# gimbal.net
KiCad netlist of a schematic drawn in EAGLE
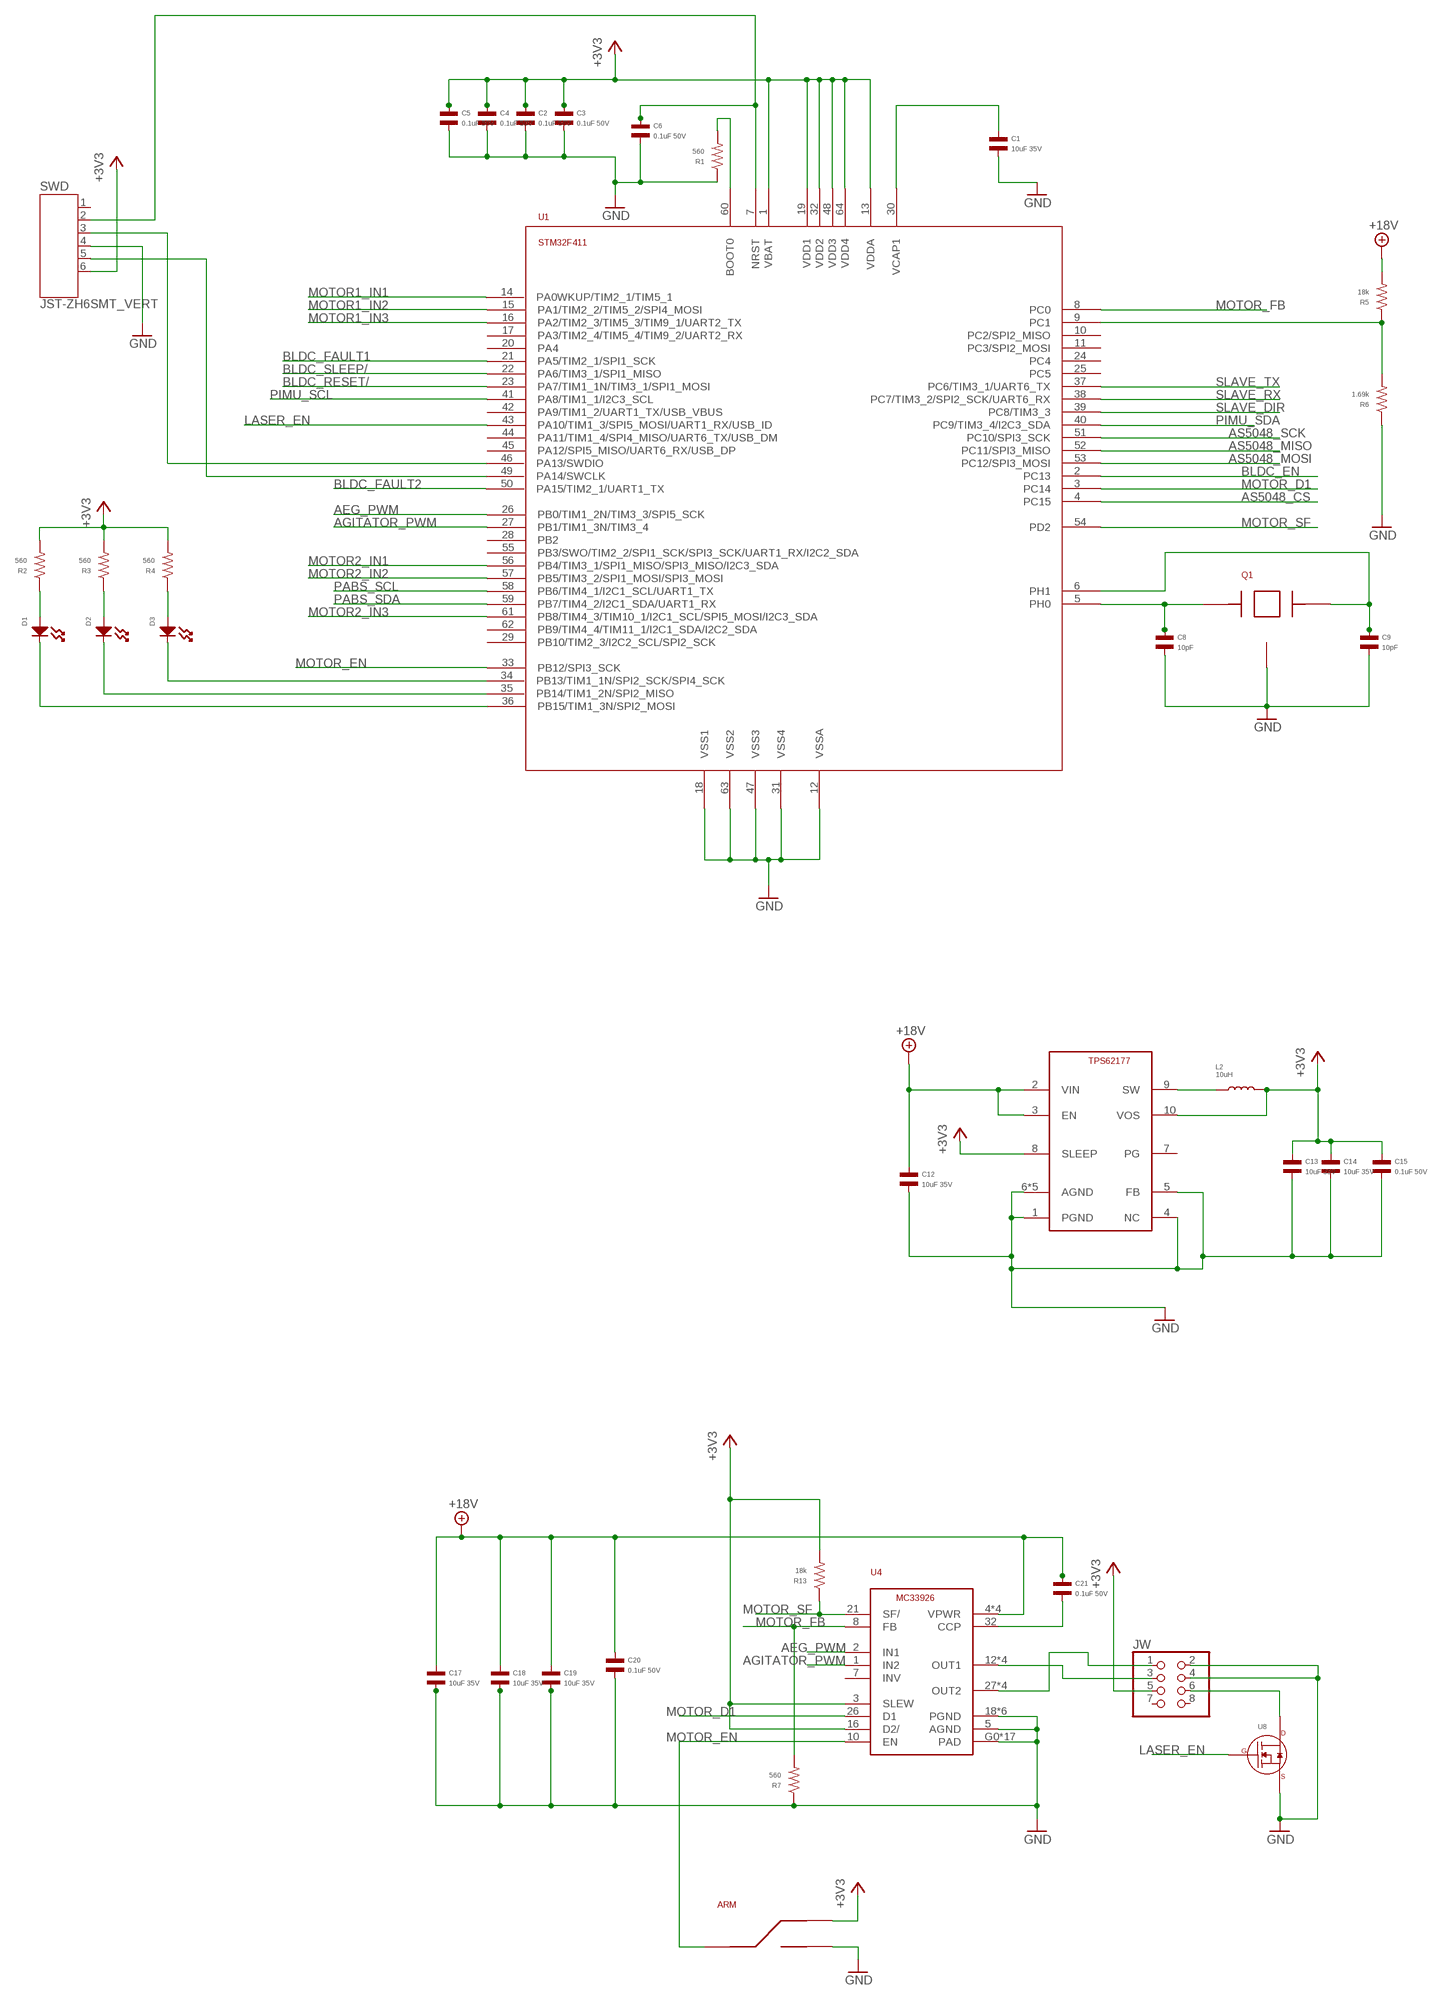
[diagram p0: schematic, sheet 1, part 1 of 2]
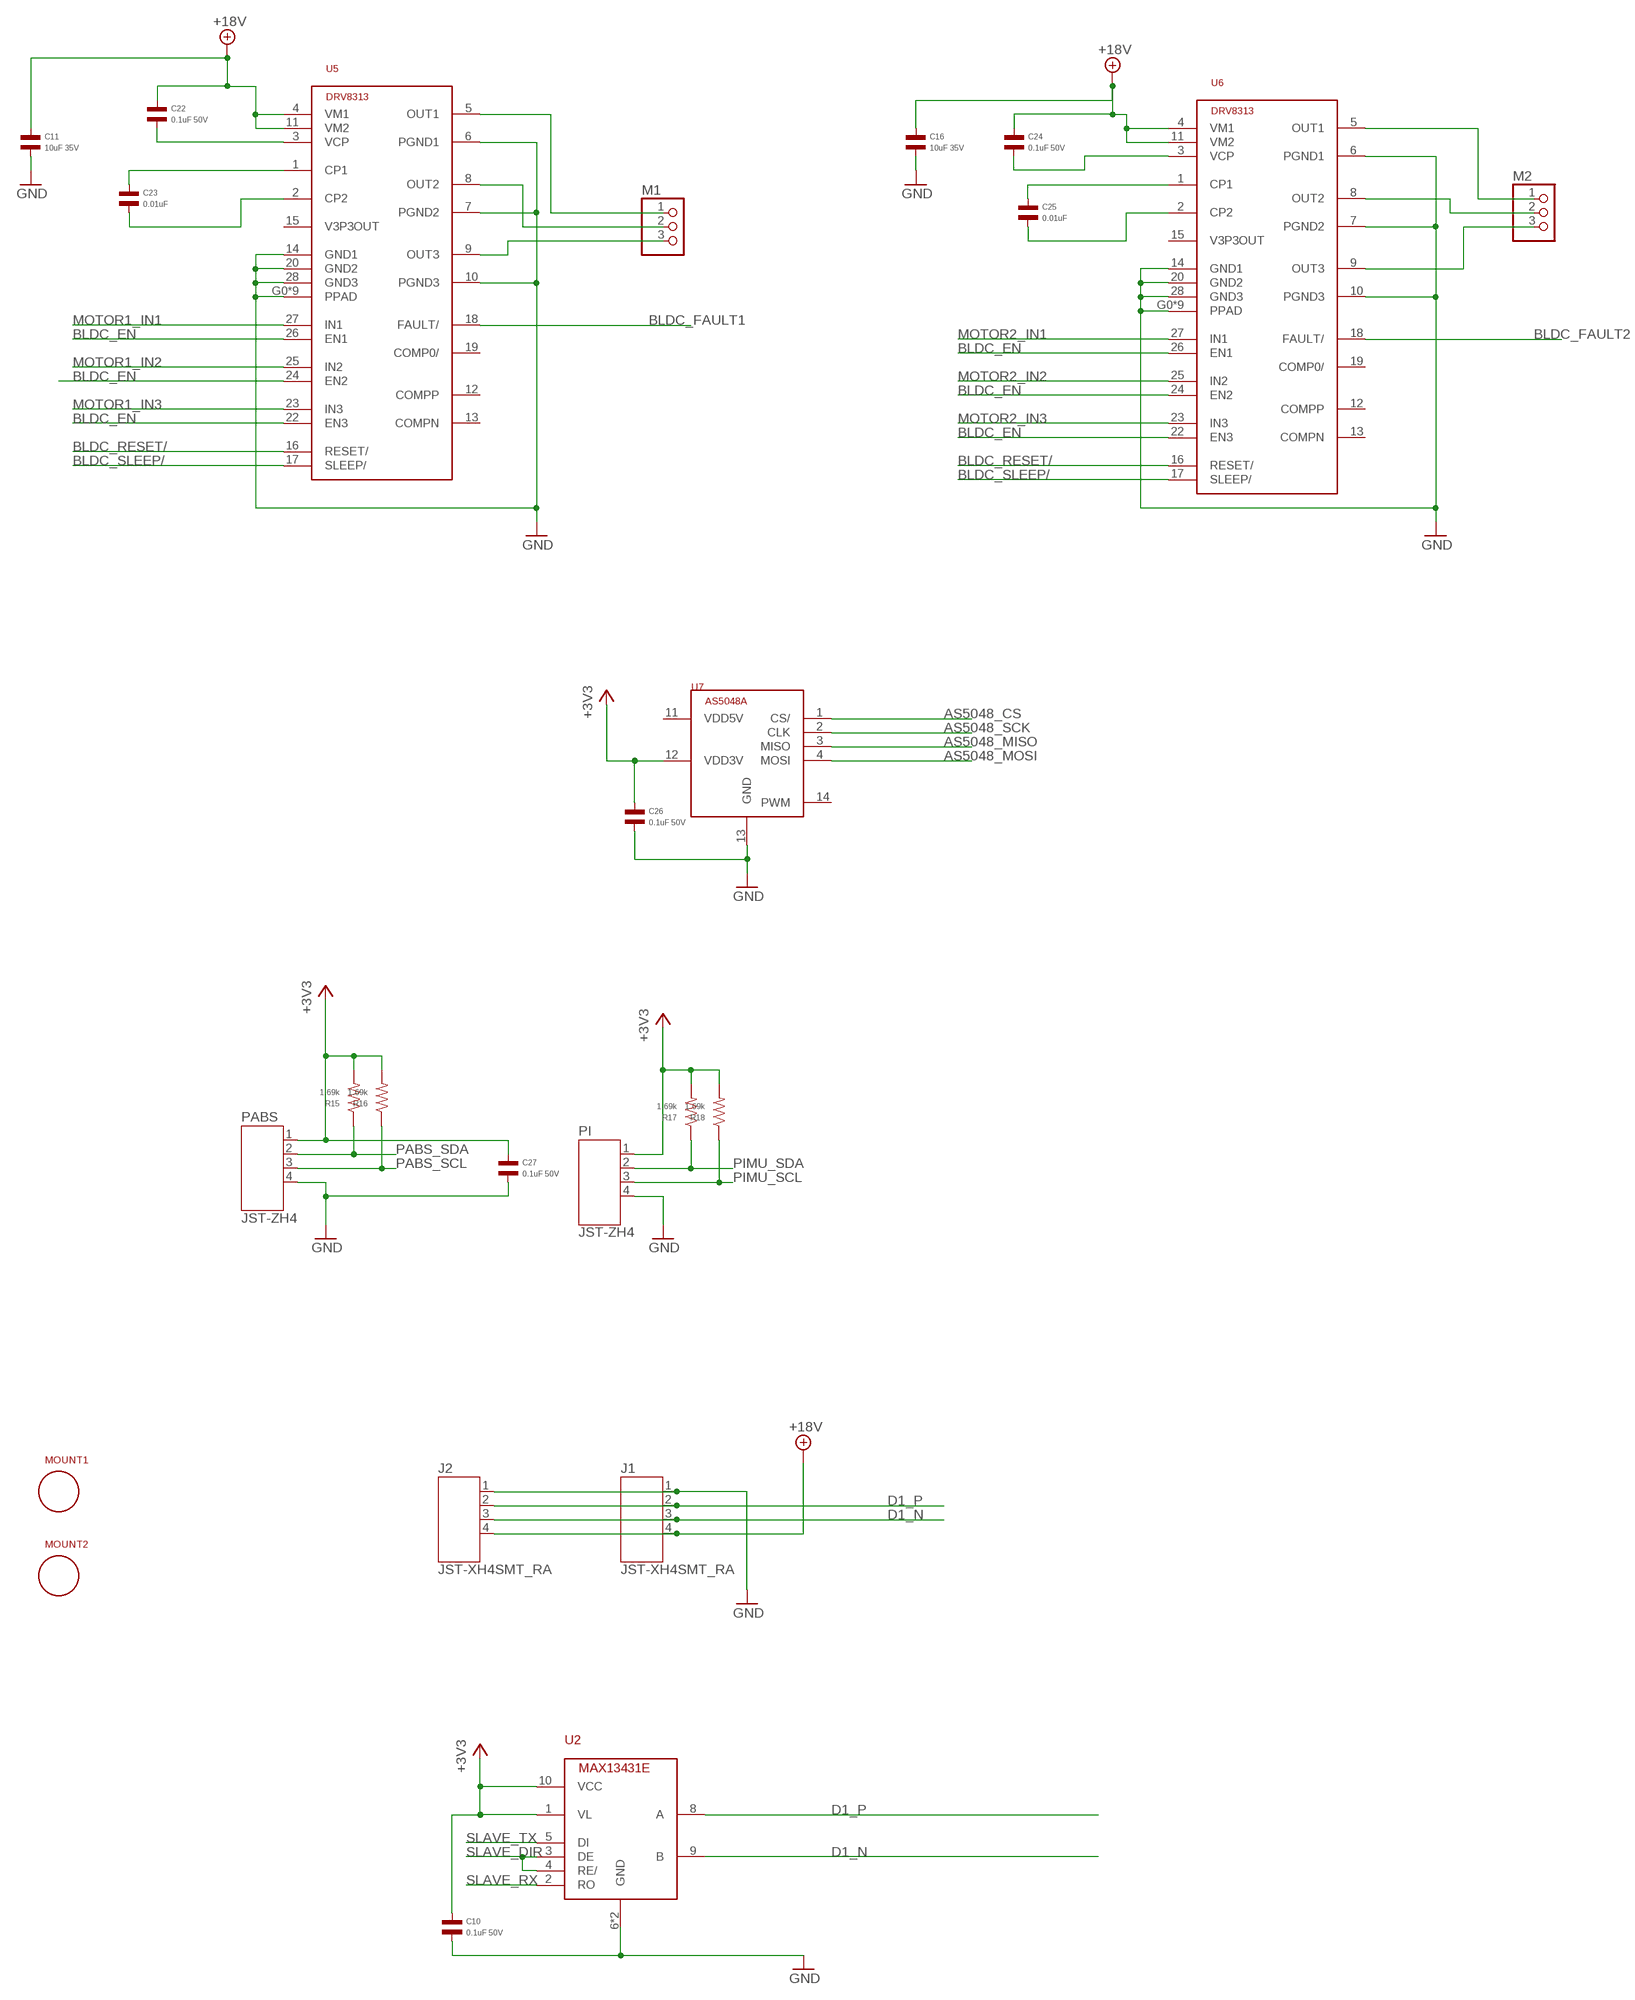
[diagram p1: schematic, sheet 1, part 2 of 2]

(export (version "E")
  (design (tool "Eeschema 10.0.6"))
  (components
    (comp (ref "ARM")
      (value "SLIDE_SWITCHJS_SUB_SWITCH")
      (footprint "eagle-import:JS_SUB_SWITCH")
      (fields (field (name "MPN") "JS102011SAQN"))
      (libsource (lib "eagle-import") (part "SLIDE_SWITCHJS_SUB_SWITCH"))
    )
    (comp (ref "C1")
      (value "10uF 35V")
      (footprint "eagle-import:C1206")
      (fields (field (name "MF") "TDK") (field (name "MPN") "CGA5L1X7R1V106M160AE"))
      (libsource (lib "eagle-import") (part "CAPACITOR_NP_1206"))
    )
    (comp (ref "C2")
      (value "0.1uF 50V")
      (footprint "eagle-import:C0402")
      (fields (field (name "MF") "Walsin") (field (name "MPN") "0402B104K500CT"))
      (libsource (lib "eagle-import") (part "CAPACITOR_NP_0402"))
    )
    (comp (ref "C3")
      (value "0.1uF 50V")
      (footprint "eagle-import:C0402")
      (fields (field (name "MF") "Walsin") (field (name "MPN") "0402B104K500CT"))
      (libsource (lib "eagle-import") (part "CAPACITOR_NP_0402"))
    )
    (comp (ref "C4")
      (value "0.1uF 50V")
      (footprint "eagle-import:C0402")
      (fields (field (name "MF") "Walsin") (field (name "MPN") "0402B104K500CT"))
      (libsource (lib "eagle-import") (part "CAPACITOR_NP_0402"))
    )
    (comp (ref "C5")
      (value "0.1uF 50V")
      (footprint "eagle-import:C0402")
      (fields (field (name "MF") "Walsin") (field (name "MPN") "0402B104K500CT"))
      (libsource (lib "eagle-import") (part "CAPACITOR_NP_0402"))
    )
    (comp (ref "C6")
      (value "0.1uF 50V")
      (footprint "eagle-import:C0402")
      (fields (field (name "MF") "Walsin") (field (name "MPN") "0402B104K500CT"))
      (libsource (lib "eagle-import") (part "CAPACITOR_NP_0402"))
    )
    (comp (ref "C8")
      (value "10pF")
      (footprint "eagle-import:C0603")
      (fields (field (name "HOUSEPART") "YES") (field (name "MPN") "MF-CAP-0603-10pF"))
      (libsource (lib "eagle-import") (part "CAPACITOR_NP_0603"))
    )
    (comp (ref "C9")
      (value "10pF")
      (footprint "eagle-import:C0603")
      (fields (field (name "HOUSEPART") "YES") (field (name "MPN") "MF-CAP-0603-10pF"))
      (libsource (lib "eagle-import") (part "CAPACITOR_NP_0603"))
    )
    (comp (ref "C10")
      (value "0.1uF 50V")
      (footprint "eagle-import:C0402")
      (fields (field (name "MF") "Walsin") (field (name "MPN") "0402B104K500CT"))
      (libsource (lib "eagle-import") (part "CAPACITOR_NP_0402"))
    )
    (comp (ref "C11")
      (value "10uF 35V")
      (footprint "eagle-import:C1206")
      (fields (field (name "MF") "TDK") (field (name "MPN") "CGA5L1X7R1V106M160AE"))
      (libsource (lib "eagle-import") (part "CAPACITOR_NP_1206"))
    )
    (comp (ref "C12")
      (value "10uF 35V")
      (footprint "eagle-import:C1206")
      (fields (field (name "MF") "TDK") (field (name "MPN") "CGA5L1X7R1V106M160AE"))
      (libsource (lib "eagle-import") (part "CAPACITOR_NP_1206"))
    )
    (comp (ref "C13")
      (value "10uF 35V")
      (footprint "eagle-import:C1206")
      (fields (field (name "MF") "TDK") (field (name "MPN") "CGA5L1X7R1V106M160AE"))
      (libsource (lib "eagle-import") (part "CAPACITOR_NP_1206"))
    )
    (comp (ref "C14")
      (value "10uF 35V")
      (footprint "eagle-import:C1206")
      (fields (field (name "MF") "TDK") (field (name "MPN") "CGA5L1X7R1V106M160AE"))
      (libsource (lib "eagle-import") (part "CAPACITOR_NP_1206"))
    )
    (comp (ref "C15")
      (value "0.1uF 50V")
      (footprint "eagle-import:C0402")
      (fields (field (name "MF") "Walsin") (field (name "MPN") "0402B104K500CT"))
      (libsource (lib "eagle-import") (part "CAPACITOR_NP_0402"))
    )
    (comp (ref "C16")
      (value "10uF 35V")
      (footprint "eagle-import:C1206")
      (fields (field (name "MF") "TDK") (field (name "MPN") "CGA5L1X7R1V106M160AE"))
      (libsource (lib "eagle-import") (part "CAPACITOR_NP_1206"))
    )
    (comp (ref "C17")
      (value "10uF 35V")
      (footprint "eagle-import:C1206")
      (fields (field (name "MF") "TDK") (field (name "MPN") "CGA5L1X7R1V106M160AE"))
      (libsource (lib "eagle-import") (part "CAPACITOR_NP_1206"))
    )
    (comp (ref "C18")
      (value "10uF 35V")
      (footprint "eagle-import:C1206")
      (fields (field (name "MF") "TDK") (field (name "MPN") "CGA5L1X7R1V106M160AE"))
      (libsource (lib "eagle-import") (part "CAPACITOR_NP_1206"))
    )
    (comp (ref "C19")
      (value "10uF 35V")
      (footprint "eagle-import:C1206")
      (fields (field (name "MF") "TDK") (field (name "MPN") "CGA5L1X7R1V106M160AE"))
      (libsource (lib "eagle-import") (part "CAPACITOR_NP_1206"))
    )
    (comp (ref "C20")
      (value "0.1uF 50V")
      (footprint "eagle-import:C0402")
      (fields (field (name "MF") "Walsin") (field (name "MPN") "0402B104K500CT"))
      (libsource (lib "eagle-import") (part "CAPACITOR_NP_0402"))
    )
    (comp (ref "C21")
      (value "0.1uF 50V")
      (footprint "eagle-import:C0402")
      (fields (field (name "MF") "Walsin") (field (name "MPN") "0402B104K500CT"))
      (libsource (lib "eagle-import") (part "CAPACITOR_NP_0402"))
    )
    (comp (ref "C22")
      (value "0.1uF 50V")
      (footprint "eagle-import:C0402")
      (fields (field (name "MF") "Walsin") (field (name "MPN") "0402B104K500CT"))
      (libsource (lib "eagle-import") (part "CAPACITOR_NP_0402"))
    )
    (comp (ref "C23")
      (value "0.01uF")
      (footprint "eagle-import:C0603")
      (fields (field (name "HOUSEPART") "YES") (field (name "MPN") "MF-CAP-0603-0.01uF"))
      (libsource (lib "eagle-import") (part "CAPACITOR_NP_0603"))
    )
    (comp (ref "C24")
      (value "0.1uF 50V")
      (footprint "eagle-import:C0402")
      (fields (field (name "MF") "Walsin") (field (name "MPN") "0402B104K500CT"))
      (libsource (lib "eagle-import") (part "CAPACITOR_NP_0402"))
    )
    (comp (ref "C25")
      (value "0.01uF")
      (footprint "eagle-import:C0603")
      (fields (field (name "HOUSEPART") "YES") (field (name "MPN") "MF-CAP-0603-0.01uF"))
      (libsource (lib "eagle-import") (part "CAPACITOR_NP_0603"))
    )
    (comp (ref "C26")
      (value "0.1uF 50V")
      (footprint "eagle-import:C0402")
      (fields (field (name "MF") "Walsin") (field (name "MPN") "0402B104K500CT"))
      (libsource (lib "eagle-import") (part "CAPACITOR_NP_0402"))
    )
    (comp (ref "C27")
      (value "0.1uF 50V")
      (footprint "eagle-import:C0402")
      (fields (field (name "MF") "Walsin") (field (name "MPN") "0402B104K500CT"))
      (libsource (lib "eagle-import") (part "CAPACITOR_NP_0402"))
    )
    (comp (ref "D1")
      (value "LED_SINGLE-0603-RED")
      (footprint "eagle-import:LED0603")
      (fields (field (name "HOUSEPART") "YES") (field (name "MPN") "MF-LED-0603-RED"))
      (libsource (lib "eagle-import") (part "LED_SINGLE-0603-RED"))
    )
    (comp (ref "D2")
      (value "LED_SINGLE-0603-RED")
      (footprint "eagle-import:LED0603")
      (fields (field (name "HOUSEPART") "YES") (field (name "MPN") "MF-LED-0603-RED"))
      (libsource (lib "eagle-import") (part "LED_SINGLE-0603-RED"))
    )
    (comp (ref "D3")
      (value "LED_SINGLE-0603-RED")
      (footprint "eagle-import:LED0603")
      (fields (field (name "HOUSEPART") "YES") (field (name "MPN") "MF-LED-0603-RED"))
      (libsource (lib "eagle-import") (part "LED_SINGLE-0603-RED"))
    )
    (comp (ref "J1")
      (value "JST-XH4SMT_RA")
      (footprint "eagle-import:JST_XH_SMT_RA_4")
      (fields (field (name "MF") "JST") (field (name "MPN") "S4B-XH-SM4-TB(LF)(SN)"))
      (libsource (lib "eagle-import") (part "JST-XH4SMT_RA"))
    )
    (comp (ref "J2")
      (value "JST-XH4SMT_RA")
      (footprint "eagle-import:JST_XH_SMT_RA_4")
      (fields (field (name "MF") "JST") (field (name "MPN") "S4B-XH-SM4-TB(LF)(SN)"))
      (libsource (lib "eagle-import") (part "JST-XH4SMT_RA"))
    )
    (comp (ref "JW")
      (value "PINHD-2X4")
      (footprint "eagle-import:2X04")
      (libsource (lib "eagle-import") (part "PINHD-2X4"))
    )
    (comp (ref "L2")
      (value "10uH")
      (footprint "eagle-import:L1210")
      (fields
        (field (name "HOUSEPART") "1")
        (field (name "MPN") "MF-IND-1210-10uH")
        (field (name "POPULATE") "1")
      )
      (libsource (lib "eagle-import") (part "INDUCTOR_1210"))
    )
    (comp (ref "M1")
      (value "PINHD-1X3")
      (footprint "eagle-import:1X03")
      (libsource (lib "eagle-import") (part "PINHD-1X3"))
    )
    (comp (ref "M2")
      (value "PINHD-1X3")
      (footprint "eagle-import:1X03")
      (libsource (lib "eagle-import") (part "PINHD-1X3"))
    )
    (comp (ref "MOUNT1")
      (value "M3_MOTOR_MOUNT")
      (footprint "eagle-import:M3_MOTOR_MOUNT")
      (libsource (lib "eagle-import") (part "M3_MOTOR_MOUNT"))
    )
    (comp (ref "MOUNT2")
      (value "M3_MOTOR_MOUNT")
      (footprint "eagle-import:M3_MOTOR_MOUNT")
      (libsource (lib "eagle-import") (part "M3_MOTOR_MOUNT"))
    )
    (comp (ref "PABS")
      (value "JST-ZH4")
      (footprint "eagle-import:JST_ZH_SMT_VERT_4")
      (fields (field (name "MF") "JST") (field (name "MPN") "B4B-ZR-SM4-TF(LF)(SN)"))
      (libsource (lib "eagle-import") (part "JST-ZH4"))
    )
    (comp (ref "PI")
      (value "JST-ZH4")
      (footprint "eagle-import:JST_ZH_SMT_VERT_4")
      (fields (field (name "MF") "JST") (field (name "MPN") "B4B-ZR-SM4-TF(LF)(SN)"))
      (libsource (lib "eagle-import") (part "JST-ZH4"))
    )
    (comp (ref "Q1")
      (value "CRYSTALABM3B")
      (footprint "eagle-import:ABM3B")
      (fields (field (name "MPN") "ABM3B-8.000MHZ-10-1-U-T"))
      (libsource (lib "eagle-import") (part "CRYSTALABM3B"))
    )
    (comp (ref "R1")
      (value "560")
      (footprint "eagle-import:R0603")
      (fields (field (name "HOUSEPART") "YES") (field (name "MPN") "MF-RES-0603-560"))
      (libsource (lib "eagle-import") (part "RESISTOR_0603"))
    )
    (comp (ref "R2")
      (value "560")
      (footprint "eagle-import:R0603")
      (fields (field (name "HOUSEPART") "YES") (field (name "MPN") "MF-RES-0603-560"))
      (libsource (lib "eagle-import") (part "RESISTOR_0603"))
    )
    (comp (ref "R3")
      (value "560")
      (footprint "eagle-import:R0603")
      (fields (field (name "HOUSEPART") "YES") (field (name "MPN") "MF-RES-0603-560"))
      (libsource (lib "eagle-import") (part "RESISTOR_0603"))
    )
    (comp (ref "R4")
      (value "560")
      (footprint "eagle-import:R0603")
      (fields (field (name "HOUSEPART") "YES") (field (name "MPN") "MF-RES-0603-560"))
      (libsource (lib "eagle-import") (part "RESISTOR_0603"))
    )
    (comp (ref "R5")
      (value "18k")
      (footprint "eagle-import:R0603")
      (fields (field (name "HOUSEPART") "YES") (field (name "MPN") "MF-RES-0603-18K"))
      (libsource (lib "eagle-import") (part "RESISTOR_0603"))
    )
    (comp (ref "R6")
      (value "1.69k")
      (footprint "eagle-import:R0603")
      (fields (field (name "HOUSEPART") "YES") (field (name "MPN") "MF-RES-0603-1.69K"))
      (libsource (lib "eagle-import") (part "RESISTOR_0603"))
    )
    (comp (ref "R7")
      (value "560")
      (footprint "eagle-import:R0603")
      (fields (field (name "HOUSEPART") "YES") (field (name "MPN") "MF-RES-0603-560"))
      (libsource (lib "eagle-import") (part "RESISTOR_0603"))
    )
    (comp (ref "R13")
      (value "18k")
      (footprint "eagle-import:R0603")
      (fields (field (name "HOUSEPART") "YES") (field (name "MPN") "MF-RES-0603-18K"))
      (libsource (lib "eagle-import") (part "RESISTOR_0603"))
    )
    (comp (ref "R15")
      (value "1.69k")
      (footprint "eagle-import:R0603")
      (fields (field (name "HOUSEPART") "YES") (field (name "MPN") "MF-RES-0603-1.69K"))
      (libsource (lib "eagle-import") (part "RESISTOR_0603"))
    )
    (comp (ref "R16")
      (value "1.69k")
      (footprint "eagle-import:R0603")
      (fields (field (name "HOUSEPART") "YES") (field (name "MPN") "MF-RES-0603-1.69K"))
      (libsource (lib "eagle-import") (part "RESISTOR_0603"))
    )
    (comp (ref "R17")
      (value "1.69k")
      (footprint "eagle-import:R0603")
      (fields (field (name "HOUSEPART") "YES") (field (name "MPN") "MF-RES-0603-1.69K"))
      (libsource (lib "eagle-import") (part "RESISTOR_0603"))
    )
    (comp (ref "R18")
      (value "1.69k")
      (footprint "eagle-import:R0603")
      (fields (field (name "HOUSEPART") "YES") (field (name "MPN") "MF-RES-0603-1.69K"))
      (libsource (lib "eagle-import") (part "RESISTOR_0603"))
    )
    (comp (ref "SWD")
      (value "JST-ZH6SMT_VERT")
      (footprint "eagle-import:JST_B6B-ZR-SM4-TF(LF)(SN)")
      (fields (field (name "MF") "JST") (field (name "MPN") "B6B-ZR-SM4-TF(LF)(SN)"))
      (libsource (lib "eagle-import") (part "JST-ZH6SMT_VERT"))
    )
    (comp (ref "U1")
      (value "STM32F4R_64PIN")
      (footprint "eagle-import:LQFP64")
      (fields (field (name "MF") "ST") (field (name "MPN") "STM32F411RET6"))
      (libsource (lib "eagle-import") (part "STM32F4R_64PIN"))
    )
    (comp (ref "U2")
      (value "MAX13431E")
      (footprint "eagle-import:TDFN10")
      (fields (field (name "MF") "Maxim") (field (name "MPN") "MAX13431EETB+T"))
      (libsource (lib "eagle-import") (part "MAX13431E"))
    )
    (comp (ref "U3")
      (value "TPS62177WSON10")
      (footprint "eagle-import:WSON10")
      (fields (field (name "MF") "TI") (field (name "MPN") "TPS62177DQCR"))
      (libsource (lib "eagle-import") (part "TPS62177WSON10"))
    )
    (comp (ref "U4")
      (value "MC33926")
      (footprint "eagle-import:PQFN32")
      (fields (field (name "MF") "Freescale") (field (name "MPN") "MC33926PNBR2"))
      (libsource (lib "eagle-import") (part "MC33926"))
    )
    (comp (ref "U5")
      (value "DRV8313")
      (footprint "eagle-import:HTSSOP28")
      (fields (field (name "MF") "TI") (field (name "MPN") "DRV8313PWP"))
      (libsource (lib "eagle-import") (part "DRV8313"))
    )
    (comp (ref "U6")
      (value "DRV8313")
      (footprint "eagle-import:HTSSOP28")
      (fields (field (name "MF") "TI") (field (name "MPN") "DRV8313PWP"))
      (libsource (lib "eagle-import") (part "DRV8313"))
    )
    (comp (ref "U7")
      (value "AS5048A")
      (footprint "eagle-import:TSSOP14")
      (fields (field (name "MF") "AMS") (field (name "MPN") "AS5047P-ATSM"))
      (libsource (lib "eagle-import") (part "AS5048A"))
    )
    (comp (ref "U8")
      (value "N-CHANNEL_FET_SOT-23-3")
      (footprint "eagle-import:SOT-23-3")
      (fields (field (name "HOUSEPART") "YES") (field (name "MPN") "MF-DSC-SOT233-BSS138"))
      (libsource (lib "eagle-import") (part "N-CHANNEL_FET_SOT-23-3"))
    )
  )
  (nets
    (net (code "1") (name "+3V3") (class "Default")
      (node (ref "ARM") (pin "1") (pinfunction "1_1") (pintype "bidirectional"))
      (node (ref "C10") (pin "P$1") (pinfunction "P$1_P$1") (pintype "passive"))
      (node (ref "C13") (pin "P$1") (pinfunction "P$1_P$1") (pintype "passive"))
      (node (ref "C14") (pin "P$1") (pinfunction "P$1_P$1") (pintype "passive"))
      (node (ref "C15") (pin "P$1") (pinfunction "P$1_P$1") (pintype "passive"))
      (node (ref "C2") (pin "P$1") (pinfunction "P$1_P$1") (pintype "passive"))
      (node (ref "C26") (pin "P$1") (pinfunction "P$1_P$1") (pintype "passive"))
      (node (ref "C27") (pin "P$1") (pinfunction "P$1_P$1") (pintype "passive"))
      (node (ref "C3") (pin "P$1") (pinfunction "P$1_P$1") (pintype "passive"))
      (node (ref "C4") (pin "P$1") (pinfunction "P$1_P$1") (pintype "passive"))
      (node (ref "C5") (pin "P$1") (pinfunction "P$1_P$1") (pintype "passive"))
      (node (ref "JW") (pin "5") (pinfunction "5_5") (pintype "passive"))
      (node (ref "L2") (pin "P$2") (pinfunction "P$2_P$2") (pintype "passive"))
      (node (ref "PABS") (pin "1") (pinfunction "1_1") (pintype "passive"))
      (node (ref "PI") (pin "1") (pinfunction "1_1") (pintype "passive"))
      (node (ref "R13") (pin "P$2") (pinfunction "P$2_P$2") (pintype "passive"))
      (node (ref "R15") (pin "P$2") (pinfunction "P$2_P$2") (pintype "passive"))
      (node (ref "R16") (pin "P$2") (pinfunction "P$2_P$2") (pintype "passive"))
      (node (ref "R17") (pin "P$2") (pinfunction "P$2_P$2") (pintype "passive"))
      (node (ref "R18") (pin "P$2") (pinfunction "P$2_P$2") (pintype "passive"))
      (node (ref "R2") (pin "P$2") (pinfunction "P$2_P$2") (pintype "passive"))
      (node (ref "R3") (pin "P$2") (pinfunction "P$2_P$2") (pintype "passive"))
      (node (ref "R4") (pin "P$2") (pinfunction "P$2_P$2") (pintype "passive"))
      (node (ref "SWD") (pin "6") (pinfunction "6_6") (pintype "passive"))
      (node (ref "U1") (pin "1") (pinfunction "VBAT_1") (pintype "bidirectional"))
      (node (ref "U1") (pin "13") (pinfunction "VDDA_13") (pintype "bidirectional"))
      (node (ref "U1") (pin "19") (pinfunction "VDD1_19") (pintype "bidirectional"))
      (node (ref "U1") (pin "32") (pinfunction "VDD2_32") (pintype "bidirectional"))
      (node (ref "U1") (pin "48") (pinfunction "VDD3_48") (pintype "bidirectional"))
      (node (ref "U1") (pin "64") (pinfunction "VDD4_64") (pintype "bidirectional"))
      (node (ref "U2") (pin "1") (pinfunction "VL_1") (pintype "bidirectional"))
      (node (ref "U2") (pin "10") (pinfunction "VCC_10") (pintype "bidirectional"))
      (node (ref "U3") (pin "10") (pinfunction "VOS_10") (pintype "bidirectional"))
      (node (ref "U3") (pin "8") (pinfunction "SLEEP_8") (pintype "bidirectional"))
      (node (ref "U4") (pin "16") (pinfunction "D2/_16") (pintype "bidirectional"))
      (node (ref "U4") (pin "3") (pinfunction "SLEW_3") (pintype "bidirectional"))
      (node (ref "U7") (pin "12") (pinfunction "VDD3V_12") (pintype "bidirectional"))
    )
    (net (code "2") (name "+18V") (class "Default")
      (node (ref "C11") (pin "P$1") (pinfunction "P$1_P$1") (pintype "passive"))
      (node (ref "C12") (pin "P$1") (pinfunction "P$1_P$1") (pintype "passive"))
      (node (ref "C16") (pin "P$1") (pinfunction "P$1_P$1") (pintype "passive"))
      (node (ref "C17") (pin "P$1") (pinfunction "P$1_P$1") (pintype "passive"))
      (node (ref "C18") (pin "P$1") (pinfunction "P$1_P$1") (pintype "passive"))
      (node (ref "C19") (pin "P$1") (pinfunction "P$1_P$1") (pintype "passive"))
      (node (ref "C20") (pin "P$1") (pinfunction "P$1_P$1") (pintype "passive"))
      (node (ref "C21") (pin "P$1") (pinfunction "P$1_P$1") (pintype "passive"))
      (node (ref "C22") (pin "P$1") (pinfunction "P$1_P$1") (pintype "passive"))
      (node (ref "C24") (pin "P$1") (pinfunction "P$1_P$1") (pintype "passive"))
      (node (ref "J1") (pin "4") (pinfunction "4_4") (pintype "passive"))
      (node (ref "J2") (pin "4") (pinfunction "4_4") (pintype "passive"))
      (node (ref "R5") (pin "P$2") (pinfunction "P$2_P$2") (pintype "passive"))
      (node (ref "U3") (pin "2") (pinfunction "VIN_2") (pintype "bidirectional"))
      (node (ref "U3") (pin "3") (pinfunction "EN_3") (pintype "bidirectional"))
      (node (ref "U4") (pin "11") (pinfunction "VPWR_11") (pintype "bidirectional"))
      (node (ref "U4") (pin "31") (pinfunction "VPWR_31") (pintype "bidirectional"))
      (node (ref "U4") (pin "4") (pinfunction "VPWR_4") (pintype "bidirectional"))
      (node (ref "U4") (pin "6") (pinfunction "VPWR_6") (pintype "bidirectional"))
      (node (ref "U5") (pin "11") (pinfunction "VM2_11") (pintype "bidirectional"))
      (node (ref "U5") (pin "4") (pinfunction "VM1_4") (pintype "bidirectional"))
      (node (ref "U6") (pin "11") (pinfunction "VM2_11") (pintype "bidirectional"))
      (node (ref "U6") (pin "4") (pinfunction "VM1_4") (pintype "bidirectional"))
    )
    (net (code "3") (name "/AEG_PWM") (class "Default")
      (node (ref "U1") (pin "26") (pinfunction "PB0/TIM1_2N/TIM3_3/SPI5_SCK_26") (pintype "bidirectional"))
      (node (ref "U4") (pin "2") (pinfunction "IN1_2") (pintype "bidirectional"))
    )
    (net (code "4") (name "/AGITATOR_PWM") (class "Default")
      (node (ref "U1") (pin "27") (pinfunction "PB1/TIM1_3N/TIM3_4_27") (pintype "bidirectional"))
      (node (ref "U4") (pin "1") (pinfunction "IN2_1") (pintype "bidirectional"))
    )
    (net (code "5") (name "/AS5048_CS") (class "Default")
      (node (ref "U1") (pin "4") (pinfunction "PC15_4") (pintype "bidirectional"))
      (node (ref "U7") (pin "1") (pinfunction "CS/_1") (pintype "bidirectional"))
    )
    (net (code "6") (name "/AS5048_MISO") (class "Default")
      (node (ref "U1") (pin "52") (pinfunction "PC11/SPI3_MISO_52") (pintype "bidirectional"))
      (node (ref "U7") (pin "3") (pinfunction "MISO_3") (pintype "bidirectional"))
    )
    (net (code "7") (name "/AS5048_MOSI") (class "Default")
      (node (ref "U1") (pin "53") (pinfunction "PC12/SPI3_MOSI_53") (pintype "bidirectional"))
      (node (ref "U7") (pin "4") (pinfunction "MOSI_4") (pintype "bidirectional"))
    )
    (net (code "8") (name "/AS5048_SCK") (class "Default")
      (node (ref "U1") (pin "51") (pinfunction "PC10/SPI3_SCK_51") (pintype "bidirectional"))
      (node (ref "U7") (pin "2") (pinfunction "CLK_2") (pintype "bidirectional"))
    )
    (net (code "9") (name "/BLDC_EN") (class "Default")
      (node (ref "U1") (pin "2") (pinfunction "PC13_2") (pintype "bidirectional"))
      (node (ref "U5") (pin "22") (pinfunction "EN3_22") (pintype "bidirectional"))
      (node (ref "U5") (pin "24") (pinfunction "EN2_24") (pintype "bidirectional"))
      (node (ref "U5") (pin "26") (pinfunction "EN1_26") (pintype "bidirectional"))
      (node (ref "U6") (pin "22") (pinfunction "EN3_22") (pintype "bidirectional"))
      (node (ref "U6") (pin "24") (pinfunction "EN2_24") (pintype "bidirectional"))
      (node (ref "U6") (pin "26") (pinfunction "EN1_26") (pintype "bidirectional"))
    )
    (net (code "10") (name "/BLDC_FAULT1") (class "Default")
      (node (ref "U1") (pin "21") (pinfunction "PA5/TIM2_1/SPI1_SCK_21") (pintype "bidirectional"))
      (node (ref "U5") (pin "18") (pinfunction "FAULT/_18") (pintype "bidirectional"))
    )
    (net (code "11") (name "/BLDC_FAULT2") (class "Default")
      (node (ref "U1") (pin "50") (pinfunction "PA15/TIM2_1/UART1_TX_50") (pintype "bidirectional"))
      (node (ref "U6") (pin "18") (pinfunction "FAULT/_18") (pintype "bidirectional"))
    )
    (net (code "12") (name "/BLDC_RESET{slash}") (class "Default")
      (node (ref "U1") (pin "23") (pinfunction "PA7/TIM1_1N/TIM3_1/SPI1_MOSI_23") (pintype "bidirectional"))
      (node (ref "U5") (pin "16") (pinfunction "RESET/_16") (pintype "bidirectional"))
      (node (ref "U6") (pin "16") (pinfunction "RESET/_16") (pintype "bidirectional"))
    )
    (net (code "13") (name "/BLDC_SLEEP{slash}") (class "Default")
      (node (ref "U1") (pin "22") (pinfunction "PA6/TIM3_1/SPI1_MISO_22") (pintype "bidirectional"))
      (node (ref "U5") (pin "17") (pinfunction "SLEEP/_17") (pintype "bidirectional"))
      (node (ref "U6") (pin "17") (pinfunction "SLEEP/_17") (pintype "bidirectional"))
    )
    (net (code "14") (name "/D1_N") (class "Default")
      (node (ref "J1") (pin "3") (pinfunction "3_3") (pintype "passive"))
      (node (ref "J2") (pin "3") (pinfunction "3_3") (pintype "passive"))
      (node (ref "U2") (pin "9") (pinfunction "B_9") (pintype "bidirectional"))
    )
    (net (code "15") (name "/D1_P") (class "Default")
      (node (ref "J1") (pin "2") (pinfunction "2_2") (pintype "passive"))
      (node (ref "J2") (pin "2") (pinfunction "2_2") (pintype "passive"))
      (node (ref "U2") (pin "8") (pinfunction "A_8") (pintype "bidirectional"))
    )
    (net (code "16") (name "/LASER_EN") (class "Default")
      (node (ref "U1") (pin "43") (pinfunction "PA10/TIM1_3/SPI5_MOSI/UART1_RX/USB_ID_43") (pintype "bidirectional"))
      (node (ref "U8") (pin "P$1") (pinfunction "GATE_P$1") (pintype "bidirectional"))
    )
    (net (code "17") (name "/MOTOR1_IN1") (class "Default")
      (node (ref "U1") (pin "14") (pinfunction "PA0WKUP/TIM2_1/TIM5_1_14") (pintype "bidirectional"))
      (node (ref "U5") (pin "27") (pinfunction "IN1_27") (pintype "bidirectional"))
    )
    (net (code "18") (name "/MOTOR1_IN2") (class "Default")
      (node (ref "U1") (pin "15") (pinfunction "PA1/TIM2_2/TIM5_2/SPI4_MOSI_15") (pintype "bidirectional"))
      (node (ref "U5") (pin "25") (pinfunction "IN2_25") (pintype "bidirectional"))
    )
    (net (code "19") (name "/MOTOR1_IN3") (class "Default")
      (node (ref "U1") (pin "16") (pinfunction "PA2/TIM2_3/TIM5_3/TIM9_1/UART2_TX_16") (pintype "bidirectional"))
      (node (ref "U5") (pin "23") (pinfunction "IN3_23") (pintype "bidirectional"))
    )
    (net (code "20") (name "/MOTOR2_IN1") (class "Default")
      (node (ref "U1") (pin "56") (pinfunction "PB4/TIM3_1/SPI1_MISO/SPI3_MISO/I2C3_SDA_56") (pintype "bidirectional"))
      (node (ref "U6") (pin "27") (pinfunction "IN1_27") (pintype "bidirectional"))
    )
    (net (code "21") (name "/MOTOR2_IN2") (class "Default")
      (node (ref "U1") (pin "57") (pinfunction "PB5/TIM3_2/SPI1_MOSI/SPI3_MOSI_57") (pintype "bidirectional"))
      (node (ref "U6") (pin "25") (pinfunction "IN2_25") (pintype "bidirectional"))
    )
    (net (code "22") (name "/MOTOR2_IN3") (class "Default")
      (node (ref "U1") (pin "61") (pinfunction "PB8/TIM4_3/TIM10_1/I2C1_SCL/SPI5_MOSI/I2C3_SDA_61") (pintype "bidirectional"))
      (node (ref "U6") (pin "23") (pinfunction "IN3_23") (pintype "bidirectional"))
    )
    (net (code "23") (name "/MOTOR_D1") (class "Default")
      (node (ref "U1") (pin "3") (pinfunction "PC14_3") (pintype "bidirectional"))
      (node (ref "U4") (pin "26") (pinfunction "D1_26") (pintype "bidirectional"))
    )
    (net (code "24") (name "/MOTOR_EN") (class "Default")
      (node (ref "ARM") (pin "2") (pinfunction "2_2") (pintype "bidirectional"))
      (node (ref "U1") (pin "33") (pinfunction "PB12/SPI3_SCK_33") (pintype "bidirectional"))
      (node (ref "U4") (pin "10") (pinfunction "EN_10") (pintype "bidirectional"))
    )
    (net (code "25") (name "/MOTOR_FB") (class "Default")
      (node (ref "R7") (pin "P$2") (pinfunction "P$2_P$2") (pintype "passive"))
      (node (ref "U1") (pin "8") (pinfunction "PC0_8") (pintype "bidirectional"))
      (node (ref "U4") (pin "8") (pinfunction "FB_8") (pintype "bidirectional"))
    )
    (net (code "26") (name "/MOTOR_SF") (class "Default")
      (node (ref "R13") (pin "P$1") (pinfunction "P$1_P$1") (pintype "passive"))
      (node (ref "U1") (pin "54") (pinfunction "PD2_54") (pintype "bidirectional"))
      (node (ref "U4") (pin "21") (pinfunction "SF/_21") (pintype "bidirectional"))
    )
    (net (code "27") (name "/PABS_SCL") (class "Default")
      (node (ref "PABS") (pin "3") (pinfunction "3_3") (pintype "passive"))
      (node (ref "R16") (pin "P$1") (pinfunction "P$1_P$1") (pintype "passive"))
      (node (ref "U1") (pin "58") (pinfunction "PB6/TIM4_1/I2C1_SCL/UART1_TX_58") (pintype "bidirectional"))
    )
    (net (code "28") (name "/PABS_SDA") (class "Default")
      (node (ref "PABS") (pin "2") (pinfunction "2_2") (pintype "passive"))
      (node (ref "R15") (pin "P$1") (pinfunction "P$1_P$1") (pintype "passive"))
      (node (ref "U1") (pin "59") (pinfunction "PB7/TIM4_2/I2C1_SDA/UART1_RX_59") (pintype "bidirectional"))
    )
    (net (code "29") (name "/PIMU_SCL") (class "Default")
      (node (ref "PI") (pin "3") (pinfunction "3_3") (pintype "passive"))
      (node (ref "R18") (pin "P$1") (pinfunction "P$1_P$1") (pintype "passive"))
      (node (ref "U1") (pin "41") (pinfunction "PA8/TIM1_1/I2C3_SCL_41") (pintype "bidirectional"))
    )
    (net (code "30") (name "/PIMU_SDA") (class "Default")
      (node (ref "PI") (pin "2") (pinfunction "2_2") (pintype "passive"))
      (node (ref "R17") (pin "P$1") (pinfunction "P$1_P$1") (pintype "passive"))
      (node (ref "U1") (pin "40") (pinfunction "PC9/TIM3_4/I2C3_SDA_40") (pintype "bidirectional"))
    )
    (net (code "31") (name "/SLAVE_DIR") (class "Default")
      (node (ref "U1") (pin "39") (pinfunction "PC8/TIM3_3_39") (pintype "bidirectional"))
      (node (ref "U2") (pin "3") (pinfunction "DE_3") (pintype "bidirectional"))
      (node (ref "U2") (pin "4") (pinfunction "RE/_4") (pintype "bidirectional"))
    )
    (net (code "32") (name "/SLAVE_RX") (class "Default")
      (node (ref "U1") (pin "38") (pinfunction "PC7/TIM3_2/SPI2_SCK/UART6_RX_38") (pintype "bidirectional"))
      (node (ref "U2") (pin "2") (pinfunction "RO_2") (pintype "bidirectional"))
    )
    (net (code "33") (name "/SLAVE_TX") (class "Default")
      (node (ref "U1") (pin "37") (pinfunction "PC6/TIM3_1/UART6_TX_37") (pintype "bidirectional"))
      (node (ref "U2") (pin "5") (pinfunction "DI_5") (pintype "bidirectional"))
    )
    (net (code "34") (name "GND") (class "Default")
      (node (ref "ARM") (pin "3") (pinfunction "3_3") (pintype "bidirectional"))
      (node (ref "C1") (pin "P$2") (pinfunction "P$2_P$2") (pintype "passive"))
      (node (ref "C10") (pin "P$2") (pinfunction "P$2_P$2") (pintype "passive"))
      (node (ref "C11") (pin "P$2") (pinfunction "P$2_P$2") (pintype "passive"))
      (node (ref "C12") (pin "P$2") (pinfunction "P$2_P$2") (pintype "passive"))
      (node (ref "C13") (pin "P$2") (pinfunction "P$2_P$2") (pintype "passive"))
      (node (ref "C14") (pin "P$2") (pinfunction "P$2_P$2") (pintype "passive"))
      (node (ref "C15") (pin "P$2") (pinfunction "P$2_P$2") (pintype "passive"))
      (node (ref "C16") (pin "P$2") (pinfunction "P$2_P$2") (pintype "passive"))
      (node (ref "C17") (pin "P$2") (pinfunction "P$2_P$2") (pintype "passive"))
      (node (ref "C18") (pin "P$2") (pinfunction "P$2_P$2") (pintype "passive"))
      (node (ref "C19") (pin "P$2") (pinfunction "P$2_P$2") (pintype "passive"))
      (node (ref "C2") (pin "P$2") (pinfunction "P$2_P$2") (pintype "passive"))
      (node (ref "C20") (pin "P$2") (pinfunction "P$2_P$2") (pintype "passive"))
      (node (ref "C26") (pin "P$2") (pinfunction "P$2_P$2") (pintype "passive"))
      (node (ref "C27") (pin "P$2") (pinfunction "P$2_P$2") (pintype "passive"))
      (node (ref "C3") (pin "P$2") (pinfunction "P$2_P$2") (pintype "passive"))
      (node (ref "C4") (pin "P$2") (pinfunction "P$2_P$2") (pintype "passive"))
      (node (ref "C5") (pin "P$2") (pinfunction "P$2_P$2") (pintype "passive"))
      (node (ref "C6") (pin "P$2") (pinfunction "P$2_P$2") (pintype "passive"))
      (node (ref "C8") (pin "P$2") (pinfunction "P$2_P$2") (pintype "passive"))
      (node (ref "C9") (pin "P$2") (pinfunction "P$2_P$2") (pintype "passive"))
      (node (ref "J1") (pin "1") (pinfunction "1_1") (pintype "passive"))
      (node (ref "J2") (pin "1") (pinfunction "1_1") (pintype "passive"))
      (node (ref "JW") (pin "2") (pinfunction "2_2") (pintype "passive"))
      (node (ref "JW") (pin "4") (pinfunction "4_4") (pintype "passive"))
      (node (ref "PABS") (pin "4") (pinfunction "4_4") (pintype "passive"))
      (node (ref "PI") (pin "4") (pinfunction "4_4") (pintype "passive"))
      (node (ref "Q1") (pin "2") (pinfunction "P$3_2") (pintype "bidirectional"))
      (node (ref "Q1") (pin "4") (pinfunction "P$3_4") (pintype "bidirectional"))
      (node (ref "R1") (pin "P$1") (pinfunction "P$1_P$1") (pintype "passive"))
      (node (ref "R6") (pin "P$1") (pinfunction "P$1_P$1") (pintype "passive"))
      (node (ref "R7") (pin "P$1") (pinfunction "P$1_P$1") (pintype "passive"))
      (node (ref "SWD") (pin "4") (pinfunction "4_4") (pintype "passive"))
      (node (ref "U1") (pin "12") (pinfunction "VSSA_12") (pintype "bidirectional"))
      (node (ref "U1") (pin "18") (pinfunction "VSS1_18") (pintype "bidirectional"))
      (node (ref "U1") (pin "31") (pinfunction "VSS4_31") (pintype "bidirectional"))
      (node (ref "U1") (pin "47") (pinfunction "VSS3_47") (pintype "bidirectional"))
      (node (ref "U1") (pin "63") (pinfunction "VSS2_63") (pintype "bidirectional"))
      (node (ref "U2") (pin "6") (pinfunction "GND_6") (pintype "bidirectional"))
      (node (ref "U2") (pin "PAD") (pinfunction "GND_PAD") (pintype "bidirectional"))
      (node (ref "U3") (pin "1") (pinfunction "PGND_1") (pintype "bidirectional"))
      (node (ref "U3") (pin "4") (pinfunction "NC_4") (pintype "bidirectional"))
      (node (ref "U3") (pin "5") (pinfunction "FB_5") (pintype "bidirectional"))
      (node (ref "U3") (pin "6") (pinfunction "AGND_6") (pintype "bidirectional"))
      (node (ref "U3") (pin "P0") (pinfunction "AGND_P0") (pintype "bidirectional"))
      (node (ref "U3") (pin "P1") (pinfunction "AGND_P1") (pintype "bidirectional"))
      (node (ref "U3") (pin "P2") (pinfunction "AGND_P2") (pintype "bidirectional"))
      (node (ref "U3") (pin "P3") (pinfunction "AGND_P3") (pintype "bidirectional"))
      (node (ref "U4") (pin "18") (pinfunction "PGND_18") (pintype "bidirectional"))
      (node (ref "U4") (pin "19") (pinfunction "PGND_19") (pintype "bidirectional"))
      (node (ref "U4") (pin "20") (pinfunction "PGND_20") (pintype "bidirectional"))
      (node (ref "U4") (pin "22") (pinfunction "PGND_22") (pintype "bidirectional"))
      (node (ref "U4") (pin "23") (pinfunction "PGND_23") (pintype "bidirectional"))
      (node (ref "U4") (pin "24") (pinfunction "PGND_24") (pintype "bidirectional"))
      (node (ref "U4") (pin "5") (pinfunction "AGND_5") (pintype "bidirectional"))
      (node (ref "U4") (pin "G0") (pinfunction "PAD_G0") (pintype "bidirectional"))
      (node (ref "U4") (pin "G1") (pinfunction "PAD_G1") (pintype "bidirectional"))
      (node (ref "U4") (pin "G10") (pinfunction "PAD_G10") (pintype "bidirectional"))
      (node (ref "U4") (pin "G11") (pinfunction "PAD_G11") (pintype "bidirectional"))
      (node (ref "U4") (pin "G12") (pinfunction "PAD_G12") (pintype "bidirectional"))
      (node (ref "U4") (pin "G13") (pinfunction "PAD_G13") (pintype "bidirectional"))
      (node (ref "U4") (pin "G14") (pinfunction "PAD_G14") (pintype "bidirectional"))
      (node (ref "U4") (pin "G15") (pinfunction "PAD_G15") (pintype "bidirectional"))
      (node (ref "U4") (pin "G16") (pinfunction "PAD_G16") (pintype "bidirectional"))
      (node (ref "U4") (pin "G2") (pinfunction "PAD_G2") (pintype "bidirectional"))
      (node (ref "U4") (pin "G3") (pinfunction "PAD_G3") (pintype "bidirectional"))
      (node (ref "U4") (pin "G4") (pinfunction "PAD_G4") (pintype "bidirectional"))
      (node (ref "U4") (pin "G5") (pinfunction "PAD_G5") (pintype "bidirectional"))
      (node (ref "U4") (pin "G6") (pinfunction "PAD_G6") (pintype "bidirectional"))
      (node (ref "U4") (pin "G7") (pinfunction "PAD_G7") (pintype "bidirectional"))
      (node (ref "U4") (pin "G8") (pinfunction "PAD_G8") (pintype "bidirectional"))
      (node (ref "U4") (pin "G9") (pinfunction "PAD_G9") (pintype "bidirectional"))
      (node (ref "U5") (pin "10") (pinfunction "PGND3_10") (pintype "bidirectional"))
      (node (ref "U5") (pin "14") (pinfunction "GND1_14") (pintype "bidirectional"))
      (node (ref "U5") (pin "20") (pinfunction "GND2_20") (pintype "bidirectional"))
      (node (ref "U5") (pin "28") (pinfunction "GND3_28") (pintype "bidirectional"))
      (node (ref "U5") (pin "6") (pinfunction "PGND1_6") (pintype "bidirectional"))
      (node (ref "U5") (pin "7") (pinfunction "PGND2_7") (pintype "bidirectional"))
      (node (ref "U5") (pin "G0") (pinfunction "PPAD_G0") (pintype "bidirectional"))
      (node (ref "U5") (pin "G1") (pinfunction "PPAD_G1") (pintype "bidirectional"))
      (node (ref "U5") (pin "G2") (pinfunction "PPAD_G2") (pintype "bidirectional"))
      (node (ref "U5") (pin "G3") (pinfunction "PPAD_G3") (pintype "bidirectional"))
      (node (ref "U5") (pin "G4") (pinfunction "PPAD_G4") (pintype "bidirectional"))
      (node (ref "U5") (pin "G5") (pinfunction "PPAD_G5") (pintype "bidirectional"))
      (node (ref "U5") (pin "G6") (pinfunction "PPAD_G6") (pintype "bidirectional"))
      (node (ref "U5") (pin "G7") (pinfunction "PPAD_G7") (pintype "bidirectional"))
      (node (ref "U5") (pin "G8") (pinfunction "PPAD_G8") (pintype "bidirectional"))
      (node (ref "U6") (pin "10") (pinfunction "PGND3_10") (pintype "bidirectional"))
      (node (ref "U6") (pin "14") (pinfunction "GND1_14") (pintype "bidirectional"))
      (node (ref "U6") (pin "20") (pinfunction "GND2_20") (pintype "bidirectional"))
      (node (ref "U6") (pin "28") (pinfunction "GND3_28") (pintype "bidirectional"))
      (node (ref "U6") (pin "6") (pinfunction "PGND1_6") (pintype "bidirectional"))
      (node (ref "U6") (pin "7") (pinfunction "PGND2_7") (pintype "bidirectional"))
      (node (ref "U6") (pin "G0") (pinfunction "PPAD_G0") (pintype "bidirectional"))
      (node (ref "U6") (pin "G1") (pinfunction "PPAD_G1") (pintype "bidirectional"))
      (node (ref "U6") (pin "G2") (pinfunction "PPAD_G2") (pintype "bidirectional"))
      (node (ref "U6") (pin "G3") (pinfunction "PPAD_G3") (pintype "bidirectional"))
      (node (ref "U6") (pin "G4") (pinfunction "PPAD_G4") (pintype "bidirectional"))
      (node (ref "U6") (pin "G5") (pinfunction "PPAD_G5") (pintype "bidirectional"))
      (node (ref "U6") (pin "G6") (pinfunction "PPAD_G6") (pintype "bidirectional"))
      (node (ref "U6") (pin "G7") (pinfunction "PPAD_G7") (pintype "bidirectional"))
      (node (ref "U6") (pin "G8") (pinfunction "PPAD_G8") (pintype "bidirectional"))
      (node (ref "U7") (pin "13") (pinfunction "GND_13") (pintype "bidirectional"))
      (node (ref "U8") (pin "P$2") (pinfunction "SOURCE_P$2") (pintype "bidirectional"))
    )
    (net (code "35") (name "Net-(D1-PadANODE)") (class "Default")
      (node (ref "D1") (pin "ANODE") (pinfunction "ANODE_ANODE") (pintype "power_in"))
      (node (ref "R2") (pin "P$1") (pinfunction "P$1_P$1") (pintype "passive"))
    )
    (net (code "36") (name "Net-(D2-PadANODE)") (class "Default")
      (node (ref "D2") (pin "ANODE") (pinfunction "ANODE_ANODE") (pintype "power_in"))
      (node (ref "R3") (pin "P$1") (pinfunction "P$1_P$1") (pintype "passive"))
    )
    (net (code "37") (name "Net-(D3-PadANODE)") (class "Default")
      (node (ref "D3") (pin "ANODE") (pinfunction "ANODE_ANODE") (pintype "power_in"))
      (node (ref "R4") (pin "P$1") (pinfunction "P$1_P$1") (pintype "passive"))
    )
    (net (code "38") (name "Net-(JW-Pad1)") (class "Default")
      (node (ref "JW") (pin "1") (pinfunction "1_1") (pintype "passive"))
      (node (ref "U4") (pin "27") (pinfunction "OUT2_27") (pintype "bidirectional"))
      (node (ref "U4") (pin "28") (pinfunction "OUT2_28") (pintype "bidirectional"))
      (node (ref "U4") (pin "29") (pinfunction "OUT2_29") (pintype "bidirectional"))
      (node (ref "U4") (pin "30") (pinfunction "OUT2_30") (pintype "bidirectional"))
    )
    (net (code "39") (name "Net-(JW-Pad3)") (class "Default")
      (node (ref "JW") (pin "3") (pinfunction "3_3") (pintype "passive"))
      (node (ref "U4") (pin "12") (pinfunction "OUT1_12") (pintype "bidirectional"))
      (node (ref "U4") (pin "13") (pinfunction "OUT1_13") (pintype "bidirectional"))
      (node (ref "U4") (pin "14") (pinfunction "OUT1_14") (pintype "bidirectional"))
      (node (ref "U4") (pin "15") (pinfunction "OUT1_15") (pintype "bidirectional"))
    )
    (net (code "40") (name "Net-(Q1-P$1)") (class "Default")
      (node (ref "C8") (pin "P$1") (pinfunction "P$1_P$1") (pintype "passive"))
      (node (ref "Q1") (pin "1") (pinfunction "P$1_1") (pintype "bidirectional"))
      (node (ref "U1") (pin "5") (pinfunction "PH0_5") (pintype "bidirectional"))
    )
    (net (code "41") (name "Net-(Q1-P$2)") (class "Default")
      (node (ref "C9") (pin "P$1") (pinfunction "P$1_P$1") (pintype "passive"))
      (node (ref "Q1") (pin "3") (pinfunction "P$2_3") (pintype "bidirectional"))
      (node (ref "U1") (pin "6") (pinfunction "PH1_6") (pintype "bidirectional"))
    )
    (net (code "42") (name "Net-(U1-BOOT0)") (class "Default")
      (node (ref "R1") (pin "P$2") (pinfunction "P$2_P$2") (pintype "passive"))
      (node (ref "U1") (pin "60") (pinfunction "BOOT0_60") (pintype "bidirectional"))
    )
    (net (code "43") (name "Net-(U1-NRST)") (class "Default")
      (node (ref "C6") (pin "P$1") (pinfunction "P$1_P$1") (pintype "passive"))
      (node (ref "SWD") (pin "2") (pinfunction "2_2") (pintype "passive"))
      (node (ref "U1") (pin "7") (pinfunction "NRST_7") (pintype "bidirectional"))
    )
    (net (code "44") (name "Net-(U1-PA13{slash}SWDIO)") (class "Default")
      (node (ref "SWD") (pin "3") (pinfunction "3_3") (pintype "passive"))
      (node (ref "U1") (pin "46") (pinfunction "PA13/SWDIO_46") (pintype "bidirectional"))
    )
    (net (code "45") (name "Net-(U1-PA14{slash}SWCLK)") (class "Default")
      (node (ref "SWD") (pin "5") (pinfunction "5_5") (pintype "passive"))
      (node (ref "U1") (pin "49") (pinfunction "PA14/SWCLK_49") (pintype "bidirectional"))
    )
    (net (code "46") (name "Net-(U1-PB13{slash}TIM1_1N{slash}SPI2_SCK{slash}SPI4_SCK)") (class "Default")
      (node (ref "D3") (pin "CATHODE") (pinfunction "CATHODE_CATHODE") (pintype "power_in"))
      (node (ref "U1") (pin "34") (pinfunction "PB13/TIM1_1N/SPI2_SCK/SPI4_SCK_34") (pintype "bidirectional"))
    )
    (net (code "47") (name "Net-(U1-PB14{slash}TIM1_2N{slash}SPI2_MISO)") (class "Default")
      (node (ref "D2") (pin "CATHODE") (pinfunction "CATHODE_CATHODE") (pintype "power_in"))
      (node (ref "U1") (pin "35") (pinfunction "PB14/TIM1_2N/SPI2_MISO_35") (pintype "bidirectional"))
    )
    (net (code "48") (name "Net-(U1-PB15{slash}TIM1_3N{slash}SPI2_MOSI)") (class "Default")
      (node (ref "D1") (pin "CATHODE") (pinfunction "CATHODE_CATHODE") (pintype "power_in"))
      (node (ref "U1") (pin "36") (pinfunction "PB15/TIM1_3N/SPI2_MOSI_36") (pintype "bidirectional"))
    )
    (net (code "49") (name "Net-(U1-PC1)") (class "Default")
      (node (ref "R5") (pin "P$1") (pinfunction "P$1_P$1") (pintype "passive"))
      (node (ref "R6") (pin "P$2") (pinfunction "P$2_P$2") (pintype "passive"))
      (node (ref "U1") (pin "9") (pinfunction "PC1_9") (pintype "bidirectional"))
    )
    (net (code "50") (name "Net-(U1-VCAP1)") (class "Default")
      (node (ref "C1") (pin "P$1") (pinfunction "P$1_P$1") (pintype "passive"))
      (node (ref "U1") (pin "30") (pinfunction "VCAP1_30") (pintype "bidirectional"))
    )
    (net (code "51") (name "Net-(U3-SW)") (class "Default")
      (node (ref "L2") (pin "P$1") (pinfunction "P$1_P$1") (pintype "passive"))
      (node (ref "U3") (pin "9") (pinfunction "SW_9") (pintype "bidirectional"))
    )
    (net (code "52") (name "Net-(U4-CCP)") (class "Default")
      (node (ref "C21") (pin "P$2") (pinfunction "P$2_P$2") (pintype "passive"))
      (node (ref "U4") (pin "32") (pinfunction "CCP_32") (pintype "bidirectional"))
    )
    (net (code "53") (name "Net-(U5-CP1)") (class "Default")
      (node (ref "C23") (pin "P$1") (pinfunction "P$1_P$1") (pintype "passive"))
      (node (ref "U5") (pin "1") (pinfunction "CP1_1") (pintype "bidirectional"))
    )
    (net (code "54") (name "Net-(U5-CP2)") (class "Default")
      (node (ref "C23") (pin "P$2") (pinfunction "P$2_P$2") (pintype "passive"))
      (node (ref "U5") (pin "2") (pinfunction "CP2_2") (pintype "bidirectional"))
    )
    (net (code "55") (name "Net-(U5-OUT1)") (class "Default")
      (node (ref "M1") (pin "1") (pinfunction "1_1") (pintype "passive"))
      (node (ref "U5") (pin "5") (pinfunction "OUT1_5") (pintype "bidirectional"))
    )
    (net (code "56") (name "Net-(U5-OUT2)") (class "Default")
      (node (ref "M1") (pin "2") (pinfunction "2_2") (pintype "passive"))
      (node (ref "U5") (pin "8") (pinfunction "OUT2_8") (pintype "bidirectional"))
    )
    (net (code "57") (name "Net-(U5-OUT3)") (class "Default")
      (node (ref "M1") (pin "3") (pinfunction "3_3") (pintype "passive"))
      (node (ref "U5") (pin "9") (pinfunction "OUT3_9") (pintype "bidirectional"))
    )
    (net (code "58") (name "Net-(U5-VCP)") (class "Default")
      (node (ref "C22") (pin "P$2") (pinfunction "P$2_P$2") (pintype "passive"))
      (node (ref "U5") (pin "3") (pinfunction "VCP_3") (pintype "bidirectional"))
    )
    (net (code "59") (name "Net-(U6-CP1)") (class "Default")
      (node (ref "C25") (pin "P$1") (pinfunction "P$1_P$1") (pintype "passive"))
      (node (ref "U6") (pin "1") (pinfunction "CP1_1") (pintype "bidirectional"))
    )
    (net (code "60") (name "Net-(U6-CP2)") (class "Default")
      (node (ref "C25") (pin "P$2") (pinfunction "P$2_P$2") (pintype "passive"))
      (node (ref "U6") (pin "2") (pinfunction "CP2_2") (pintype "bidirectional"))
    )
    (net (code "61") (name "Net-(U6-OUT1)") (class "Default")
      (node (ref "M2") (pin "1") (pinfunction "1_1") (pintype "passive"))
      (node (ref "U6") (pin "5") (pinfunction "OUT1_5") (pintype "bidirectional"))
    )
    (net (code "62") (name "Net-(U6-OUT2)") (class "Default")
      (node (ref "M2") (pin "2") (pinfunction "2_2") (pintype "passive"))
      (node (ref "U6") (pin "8") (pinfunction "OUT2_8") (pintype "bidirectional"))
    )
    (net (code "63") (name "Net-(U6-OUT3)") (class "Default")
      (node (ref "M2") (pin "3") (pinfunction "3_3") (pintype "passive"))
      (node (ref "U6") (pin "9") (pinfunction "OUT3_9") (pintype "bidirectional"))
    )
    (net (code "64") (name "Net-(U6-VCP)") (class "Default")
      (node (ref "C24") (pin "P$2") (pinfunction "P$2_P$2") (pintype "passive"))
      (node (ref "U6") (pin "3") (pinfunction "VCP_3") (pintype "bidirectional"))
    )
    (net (code "65") (name "Net-(U8-DRAIN)") (class "Default")
      (node (ref "JW") (pin "6") (pinfunction "6_6") (pintype "passive"))
      (node (ref "U8") (pin "P$3") (pinfunction "DRAIN_P$3") (pintype "bidirectional"))
    )
    (net (code "66") (name "unconnected-(JW-Pad7)") (class "Default")
      (node (ref "JW") (pin "7") (pinfunction "7_7") (pintype "passive"))
    )
    (net (code "67") (name "unconnected-(JW-Pad8)") (class "Default")
      (node (ref "JW") (pin "8") (pinfunction "8_8") (pintype "passive"))
    )
    (net (code "68") (name "unconnected-(SWD-Pad1)") (class "Default")
      (node (ref "SWD") (pin "1") (pinfunction "1_1") (pintype "passive"))
    )
    (net (code "69") (name "unconnected-(U1-PA3{slash}TIM2_4{slash}TIM5_4{slash}TIM9_2{slash}UART2_RX-Pad17)") (class "Default")
      (node (ref "U1") (pin "17") (pinfunction "PA3/TIM2_4/TIM5_4/TIM9_2/UART2_RX_17") (pintype "bidirectional"))
    )
    (net (code "70") (name "unconnected-(U1-PA4-Pad20)") (class "Default")
      (node (ref "U1") (pin "20") (pinfunction "PA4_20") (pintype "bidirectional"))
    )
    (net (code "71") (name "unconnected-(U1-PA9{slash}TIM1_2{slash}UART1_TX{slash}USB_VBUS-Pad42)") (class "Default")
      (node (ref "U1") (pin "42") (pinfunction "PA9/TIM1_2/UART1_TX/USB_VBUS_42") (pintype "bidirectional"))
    )
    (net (code "72") (name "unconnected-(U1-PA11{slash}TIM1_4{slash}SPI4_MISO{slash}UART6_TX{slash}USB_DM-Pad44)") (class "Default")
      (node (ref "U1") (pin "44") (pinfunction "PA11/TIM1_4/SPI4_MISO/UART6_TX/USB_DM_44") (pintype "bidirectional"))
    )
    (net (code "73") (name "unconnected-(U1-PA12{slash}SPI5_MISO{slash}UART6_RX{slash}USB_DP-Pad45)") (class "Default")
      (node (ref "U1") (pin "45") (pinfunction "PA12/SPI5_MISO/UART6_RX/USB_DP_45") (pintype "bidirectional"))
    )
    (net (code "74") (name "unconnected-(U1-PB2-Pad28)") (class "Default")
      (node (ref "U1") (pin "28") (pinfunction "PB2_28") (pintype "bidirectional"))
    )
    (net (code "75") (name "unconnected-(U1-PB3{slash}SWO{slash}TIM2_2{slash}SPI1_SCK{slash}SPI3_SCK{slash}UART1_RX{slash}I2C2_SDA-Pad55)") (class "Default")
      (node (ref "U1") (pin "55") (pinfunction "PB3/SWO/TIM2_2/SPI1_SCK/SPI3_SCK/UART1_RX/I2C2_SDA_55") (pintype "bidirectional"))
    )
    (net (code "76") (name "unconnected-(U1-PB9{slash}TIM4_4{slash}TIM11_1{slash}I2C1_SDA{slash}I2C2_SDA-Pad62)") (class "Default")
      (node (ref "U1") (pin "62") (pinfunction "PB9/TIM4_4/TIM11_1/I2C1_SDA/I2C2_SDA_62") (pintype "bidirectional"))
    )
    (net (code "77") (name "unconnected-(U1-PB10{slash}TIM2_3{slash}I2C2_SCL{slash}SPI2_SCK-Pad29)") (class "Default")
      (node (ref "U1") (pin "29") (pinfunction "PB10/TIM2_3/I2C2_SCL/SPI2_SCK_29") (pintype "bidirectional"))
    )
    (net (code "78") (name "unconnected-(U1-PC2{slash}SPI2_MISO-Pad10)") (class "Default")
      (node (ref "U1") (pin "10") (pinfunction "PC2/SPI2_MISO_10") (pintype "bidirectional"))
    )
    (net (code "79") (name "unconnected-(U1-PC3{slash}SPI2_MOSI-Pad11)") (class "Default")
      (node (ref "U1") (pin "11") (pinfunction "PC3/SPI2_MOSI_11") (pintype "bidirectional"))
    )
    (net (code "80") (name "unconnected-(U1-PC4-Pad24)") (class "Default")
      (node (ref "U1") (pin "24") (pinfunction "PC4_24") (pintype "bidirectional"))
    )
    (net (code "81") (name "unconnected-(U1-PC5-Pad25)") (class "Default")
      (node (ref "U1") (pin "25") (pinfunction "PC5_25") (pintype "bidirectional"))
    )
    (net (code "82") (name "unconnected-(U3-PG-Pad7)") (class "Default")
      (node (ref "U3") (pin "7") (pinfunction "PG_7") (pintype "bidirectional"))
    )
    (net (code "83") (name "unconnected-(U4-INV-Pad7)") (class "Default")
      (node (ref "U4") (pin "7") (pinfunction "INV_7") (pintype "bidirectional"))
    )
    (net (code "84") (name "unconnected-(U5-COMP0{slash}-Pad19)") (class "Default")
      (node (ref "U5") (pin "19") (pinfunction "COMP0/_19") (pintype "bidirectional"))
    )
    (net (code "85") (name "unconnected-(U5-COMPN-Pad13)") (class "Default")
      (node (ref "U5") (pin "13") (pinfunction "COMPN_13") (pintype "bidirectional"))
    )
    (net (code "86") (name "unconnected-(U5-COMPP-Pad12)") (class "Default")
      (node (ref "U5") (pin "12") (pinfunction "COMPP_12") (pintype "bidirectional"))
    )
    (net (code "87") (name "unconnected-(U5-V3P3OUT-Pad15)") (class "Default")
      (node (ref "U5") (pin "15") (pinfunction "V3P3OUT_15") (pintype "bidirectional"))
    )
    (net (code "88") (name "unconnected-(U6-COMP0{slash}-Pad19)") (class "Default")
      (node (ref "U6") (pin "19") (pinfunction "COMP0/_19") (pintype "bidirectional"))
    )
    (net (code "89") (name "unconnected-(U6-COMPN-Pad13)") (class "Default")
      (node (ref "U6") (pin "13") (pinfunction "COMPN_13") (pintype "bidirectional"))
    )
    (net (code "90") (name "unconnected-(U6-COMPP-Pad12)") (class "Default")
      (node (ref "U6") (pin "12") (pinfunction "COMPP_12") (pintype "bidirectional"))
    )
    (net (code "91") (name "unconnected-(U6-V3P3OUT-Pad15)") (class "Default")
      (node (ref "U6") (pin "15") (pinfunction "V3P3OUT_15") (pintype "bidirectional"))
    )
    (net (code "92") (name "unconnected-(U7-PWM-Pad14)") (class "Default")
      (node (ref "U7") (pin "14") (pinfunction "PWM_14") (pintype "bidirectional"))
    )
    (net (code "93") (name "unconnected-(U7-VDD5V-Pad11)") (class "Default")
      (node (ref "U7") (pin "11") (pinfunction "VDD5V_11") (pintype "bidirectional"))
    )
  )
)
